# marquee_power_supply.net
KiCad netlist of a schematic drawn in EAGLE
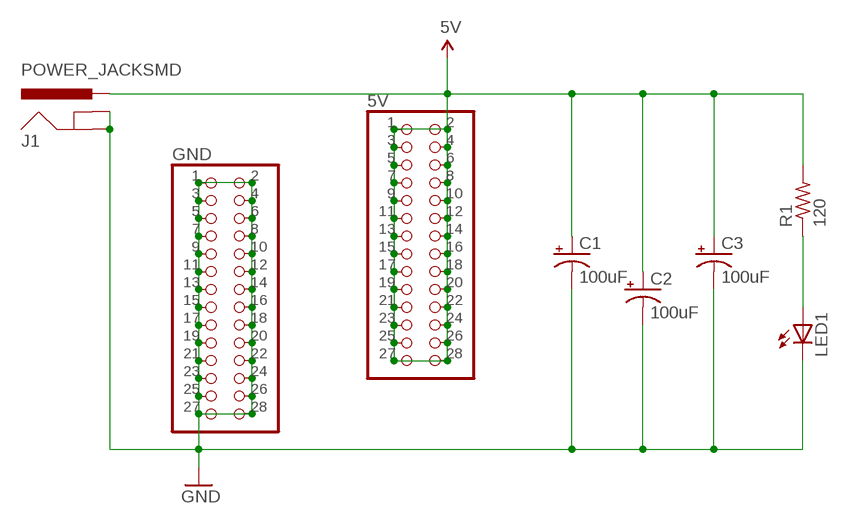
[diagram p0: schematic, sheet 1]

(export (version "E")
  (design (tool "Eeschema 10.0.6"))
  (components
    (comp (ref "5V")
      (value "PINHD-2X14")
      (footprint "eagle-import:2X14")
      (libsource (lib "eagle-import") (part "PINHD-2X14"))
    )
    (comp (ref "C1")
      (value "100uF")
      (footprint "eagle-import:CPOL-RADIAL-100UF-25V")
      (libsource (lib "eagle-import") (part "CAP_POLPTH1"))
    )
    (comp (ref "C2")
      (value "100uF")
      (footprint "eagle-import:CPOL-RADIAL-100UF-25V")
      (libsource (lib "eagle-import") (part "CAP_POLPTH1"))
    )
    (comp (ref "C3")
      (value "100uF")
      (footprint "eagle-import:CPOL-RADIAL-100UF-25V")
      (libsource (lib "eagle-import") (part "CAP_POLPTH1"))
    )
    (comp (ref "GND")
      (value "PINHD-2X14")
      (footprint "eagle-import:2X14")
      (libsource (lib "eagle-import") (part "PINHD-2X14"))
    )
    (comp (ref "J1")
      (value "POWER_JACKSMD")
      (footprint "eagle-import:POWER_JACK_SMD")
      (libsource (lib "eagle-import") (part "POWER_JACKSMD"))
    )
    (comp (ref "LED1")
      (value "LED5MM")
      (footprint "eagle-import:LED5MM")
      (libsource (lib "eagle-import") (part "LED5MM"))
    )
    (comp (ref "R1")
      (value "120")
      (footprint "eagle-import:0204_5")
      (libsource (lib "eagle-import") (part "R-US_0204/5"))
    )
  )
  (nets
    (net (code "1") (name "5V") (class "Default")
      (node (ref "5V") (pin "1") (pinfunction "1_1") (pintype "passive"))
      (node (ref "5V") (pin "10") (pinfunction "10_10") (pintype "passive"))
      (node (ref "5V") (pin "11") (pinfunction "11_11") (pintype "passive"))
      (node (ref "5V") (pin "12") (pinfunction "12_12") (pintype "passive"))
      (node (ref "5V") (pin "13") (pinfunction "13_13") (pintype "passive"))
      (node (ref "5V") (pin "14") (pinfunction "14_14") (pintype "passive"))
      (node (ref "5V") (pin "15") (pinfunction "15_15") (pintype "passive"))
      (node (ref "5V") (pin "16") (pinfunction "16_16") (pintype "passive"))
      (node (ref "5V") (pin "17") (pinfunction "17_17") (pintype "passive"))
      (node (ref "5V") (pin "18") (pinfunction "18_18") (pintype "passive"))
      (node (ref "5V") (pin "19") (pinfunction "19_19") (pintype "passive"))
      (node (ref "5V") (pin "2") (pinfunction "2_2") (pintype "passive"))
      (node (ref "5V") (pin "20") (pinfunction "20_20") (pintype "passive"))
      (node (ref "5V") (pin "21") (pinfunction "21_21") (pintype "passive"))
      (node (ref "5V") (pin "22") (pinfunction "22_22") (pintype "passive"))
      (node (ref "5V") (pin "23") (pinfunction "23_23") (pintype "passive"))
      (node (ref "5V") (pin "24") (pinfunction "24_24") (pintype "passive"))
      (node (ref "5V") (pin "25") (pinfunction "25_25") (pintype "passive"))
      (node (ref "5V") (pin "26") (pinfunction "26_26") (pintype "passive"))
      (node (ref "5V") (pin "27") (pinfunction "27_27") (pintype "passive"))
      (node (ref "5V") (pin "28") (pinfunction "28_28") (pintype "passive"))
      (node (ref "5V") (pin "3") (pinfunction "3_3") (pintype "passive"))
      (node (ref "5V") (pin "4") (pinfunction "4_4") (pintype "passive"))
      (node (ref "5V") (pin "5") (pinfunction "5_5") (pintype "passive"))
      (node (ref "5V") (pin "6") (pinfunction "6_6") (pintype "passive"))
      (node (ref "5V") (pin "7") (pinfunction "7_7") (pintype "passive"))
      (node (ref "5V") (pin "8") (pinfunction "8_8") (pintype "passive"))
      (node (ref "5V") (pin "9") (pinfunction "9_9") (pintype "passive"))
      (node (ref "C1") (pin "1") (pinfunction "+_1") (pintype "passive"))
      (node (ref "C2") (pin "1") (pinfunction "+_1") (pintype "passive"))
      (node (ref "C3") (pin "1") (pinfunction "+_1") (pintype "passive"))
      (node (ref "J1") (pin "VIN0") (pinfunction "PWR_VIN0") (pintype "bidirectional"))
      (node (ref "R1") (pin "2") (pinfunction "2_2") (pintype "passive"))
    )
    (net (code "2") (name "GND") (class "Default")
      (node (ref "C1") (pin "2") (pinfunction "-_2") (pintype "passive"))
      (node (ref "C2") (pin "2") (pinfunction "-_2") (pintype "passive"))
      (node (ref "C3") (pin "2") (pinfunction "-_2") (pintype "passive"))
      (node (ref "GND") (pin "1") (pinfunction "1_1") (pintype "passive"))
      (node (ref "GND") (pin "10") (pinfunction "10_10") (pintype "passive"))
      (node (ref "GND") (pin "11") (pinfunction "11_11") (pintype "passive"))
      (node (ref "GND") (pin "12") (pinfunction "12_12") (pintype "passive"))
      (node (ref "GND") (pin "13") (pinfunction "13_13") (pintype "passive"))
      (node (ref "GND") (pin "14") (pinfunction "14_14") (pintype "passive"))
      (node (ref "GND") (pin "15") (pinfunction "15_15") (pintype "passive"))
      (node (ref "GND") (pin "16") (pinfunction "16_16") (pintype "passive"))
      (node (ref "GND") (pin "17") (pinfunction "17_17") (pintype "passive"))
      (node (ref "GND") (pin "18") (pinfunction "18_18") (pintype "passive"))
      (node (ref "GND") (pin "19") (pinfunction "19_19") (pintype "passive"))
      (node (ref "GND") (pin "2") (pinfunction "2_2") (pintype "passive"))
      (node (ref "GND") (pin "20") (pinfunction "20_20") (pintype "passive"))
      (node (ref "GND") (pin "21") (pinfunction "21_21") (pintype "passive"))
      (node (ref "GND") (pin "22") (pinfunction "22_22") (pintype "passive"))
      (node (ref "GND") (pin "23") (pinfunction "23_23") (pintype "passive"))
      (node (ref "GND") (pin "24") (pinfunction "24_24") (pintype "passive"))
      (node (ref "GND") (pin "25") (pinfunction "25_25") (pintype "passive"))
      (node (ref "GND") (pin "26") (pinfunction "26_26") (pintype "passive"))
      (node (ref "GND") (pin "27") (pinfunction "27_27") (pintype "passive"))
      (node (ref "GND") (pin "28") (pinfunction "28_28") (pintype "passive"))
      (node (ref "GND") (pin "3") (pinfunction "3_3") (pintype "passive"))
      (node (ref "GND") (pin "4") (pinfunction "4_4") (pintype "passive"))
      (node (ref "GND") (pin "5") (pinfunction "5_5") (pintype "passive"))
      (node (ref "GND") (pin "6") (pinfunction "6_6") (pintype "passive"))
      (node (ref "GND") (pin "7") (pinfunction "7_7") (pintype "passive"))
      (node (ref "GND") (pin "8") (pinfunction "8_8") (pintype "passive"))
      (node (ref "GND") (pin "9") (pinfunction "9_9") (pintype "passive"))
      (node (ref "J1") (pin "GND") (pinfunction "GNDBREAK_GND") (pintype "bidirectional"))
      (node (ref "J1") (pin "P$4") (pinfunction "GND_P$4") (pintype "bidirectional"))
      (node (ref "LED1") (pin "K") (pinfunction "C_K") (pintype "passive"))
    )
    (net (code "3") (name "Net-(LED1-PadA)") (class "Default")
      (node (ref "LED1") (pin "A") (pinfunction "A_A") (pintype "passive"))
      (node (ref "R1") (pin "1") (pinfunction "1_1") (pintype "passive"))
    )
  )
)
